# CAN.net
KiCad netlist of a schematic drawn in Altium Designer
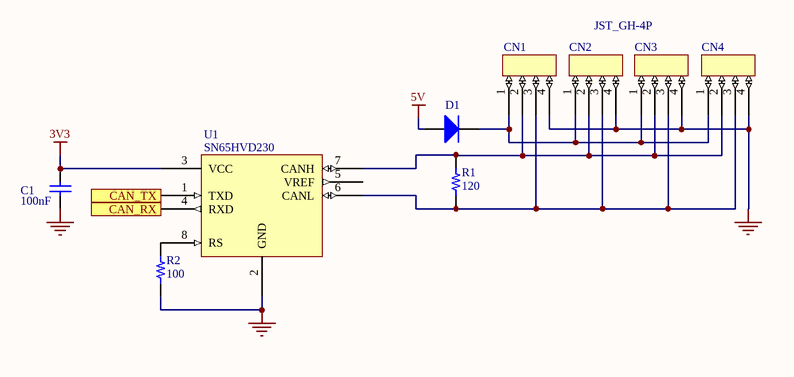
[diagram p0: CAN.SchDoc]

(export (version "E")
  (design (tool "Eeschema 10.0.6"))
  (components
    (comp (ref "C1")
      (value "100nF")
      (footprint "0402")
      (fields (field (name "Comment") "Cap") (field (name "PUBLISHER") "Altium Limited"))
      (libsource (lib "Parts") (part "Cap"))
    )
    (comp (ref "CN1")
      (value "JST_GH-4P")
      (footprint "JST_GH-4P")
      (libsource (lib "Parts") (part "JST_GH-4P"))
    )
    (comp (ref "CN2")
      (value "JST_GH-4P")
      (footprint "JST_GH-4P")
      (libsource (lib "Parts") (part "JST_GH-4P"))
    )
    (comp (ref "CN3")
      (value "JST_GH-4P")
      (footprint "JST_GH-4P")
      (libsource (lib "Parts") (part "JST_GH-4P"))
    )
    (comp (ref "CN4")
      (value "JST_GH-4P")
      (footprint "JST_GH-4P")
      (libsource (lib "Parts") (part "JST_GH-4P"))
    )
    (comp (ref "D1") (value "SS12F") (footprint "SMAF_DIODE") (libsource (lib "Parts") (part "SS12F")))
    (comp (ref "R1")
      (value "120")
      (footprint "2010_SMD_Resistor")
      (libsource (lib "Parts") (part "Resistor"))
    )
    (comp (ref "R2") (value "100") (footprint "0805 - duplicate") (libsource (lib "Parts") (part "Resistor")))
    (comp (ref "U1")
      (value "SN65HVD230")
      (footprint "SOIC8-TI_CAN")
      (description "CAN Transceiver")
      (libsource (lib "Parts") (part "SN65HVD230"))
    )
  )
  (nets
    (net (code "1") (name "/CAN_RX") (class "Default")
      (node (ref "U1") (pin "4") (pinfunction "RXD_4") (pintype "output"))
    )
    (net (code "2") (name "/CAN_TX") (class "Default")
      (node (ref "U1") (pin "1") (pinfunction "TXD_1") (pintype "input"))
    )
    (net (code "3") (name "3V3") (class "Default")
      (node (ref "C1") (pin "2") (pinfunction "2_2") (pintype "passive"))
      (node (ref "U1") (pin "3") (pinfunction "VCC_3") (pintype "power_in"))
    )
    (net (code "4") (name "5V") (class "Default")
      (node (ref "D1") (pin "1") (pinfunction "A_1") (pintype "passive"))
    )
    (net (code "5") (name "GND") (class "Default")
      (node (ref "C1") (pin "1") (pinfunction "1_1") (pintype "passive"))
      (node (ref "CN1") (pin "4") (pintype "bidirectional"))
      (node (ref "CN2") (pin "4") (pintype "bidirectional"))
      (node (ref "CN3") (pin "4") (pintype "bidirectional"))
      (node (ref "CN4") (pin "4") (pintype "bidirectional"))
      (node (ref "R2") (pin "1") (pinfunction "1_1") (pintype "passive"))
      (node (ref "U1") (pin "2") (pinfunction "GND_2") (pintype "power_in"))
    )
    (net (code "6") (name "Net-(D1-K)") (class "Default")
      (node (ref "CN1") (pin "1") (pintype "bidirectional"))
      (node (ref "CN2") (pin "1") (pintype "bidirectional"))
      (node (ref "CN3") (pin "1") (pintype "bidirectional"))
      (node (ref "CN4") (pin "1") (pintype "bidirectional"))
      (node (ref "D1") (pin "2") (pinfunction "K_2") (pintype "passive"))
    )
    (net (code "7") (name "Net-(U1-CANH)") (class "Default")
      (node (ref "CN1") (pin "2") (pintype "bidirectional"))
      (node (ref "CN2") (pin "2") (pintype "bidirectional"))
      (node (ref "CN3") (pin "2") (pintype "bidirectional"))
      (node (ref "CN4") (pin "2") (pintype "bidirectional"))
      (node (ref "R1") (pin "2") (pinfunction "2_2") (pintype "passive"))
      (node (ref "U1") (pin "7") (pinfunction "CANH_7") (pintype "bidirectional"))
    )
    (net (code "8") (name "Net-(U1-CANL)") (class "Default")
      (node (ref "CN1") (pin "3") (pintype "bidirectional"))
      (node (ref "CN2") (pin "3") (pintype "bidirectional"))
      (node (ref "CN3") (pin "3") (pintype "bidirectional"))
      (node (ref "CN4") (pin "3") (pintype "bidirectional"))
      (node (ref "R1") (pin "1") (pinfunction "1_1") (pintype "passive"))
      (node (ref "U1") (pin "6") (pinfunction "CANL_6") (pintype "bidirectional"))
    )
    (net (code "9") (name "Net-(U1-RS)") (class "Default")
      (node (ref "R2") (pin "2") (pinfunction "2_2") (pintype "passive"))
      (node (ref "U1") (pin "8") (pinfunction "RS_8") (pintype "input"))
    )
    (net (code "10") (name "unconnected-(U1-VREF-Pad5)") (class "Default")
      (node (ref "U1") (pin "5") (pinfunction "VREF_5") (pintype "output"))
    )
  )
)
